# room.net
KiCad netlist of a schematic drawn in Altium Designer
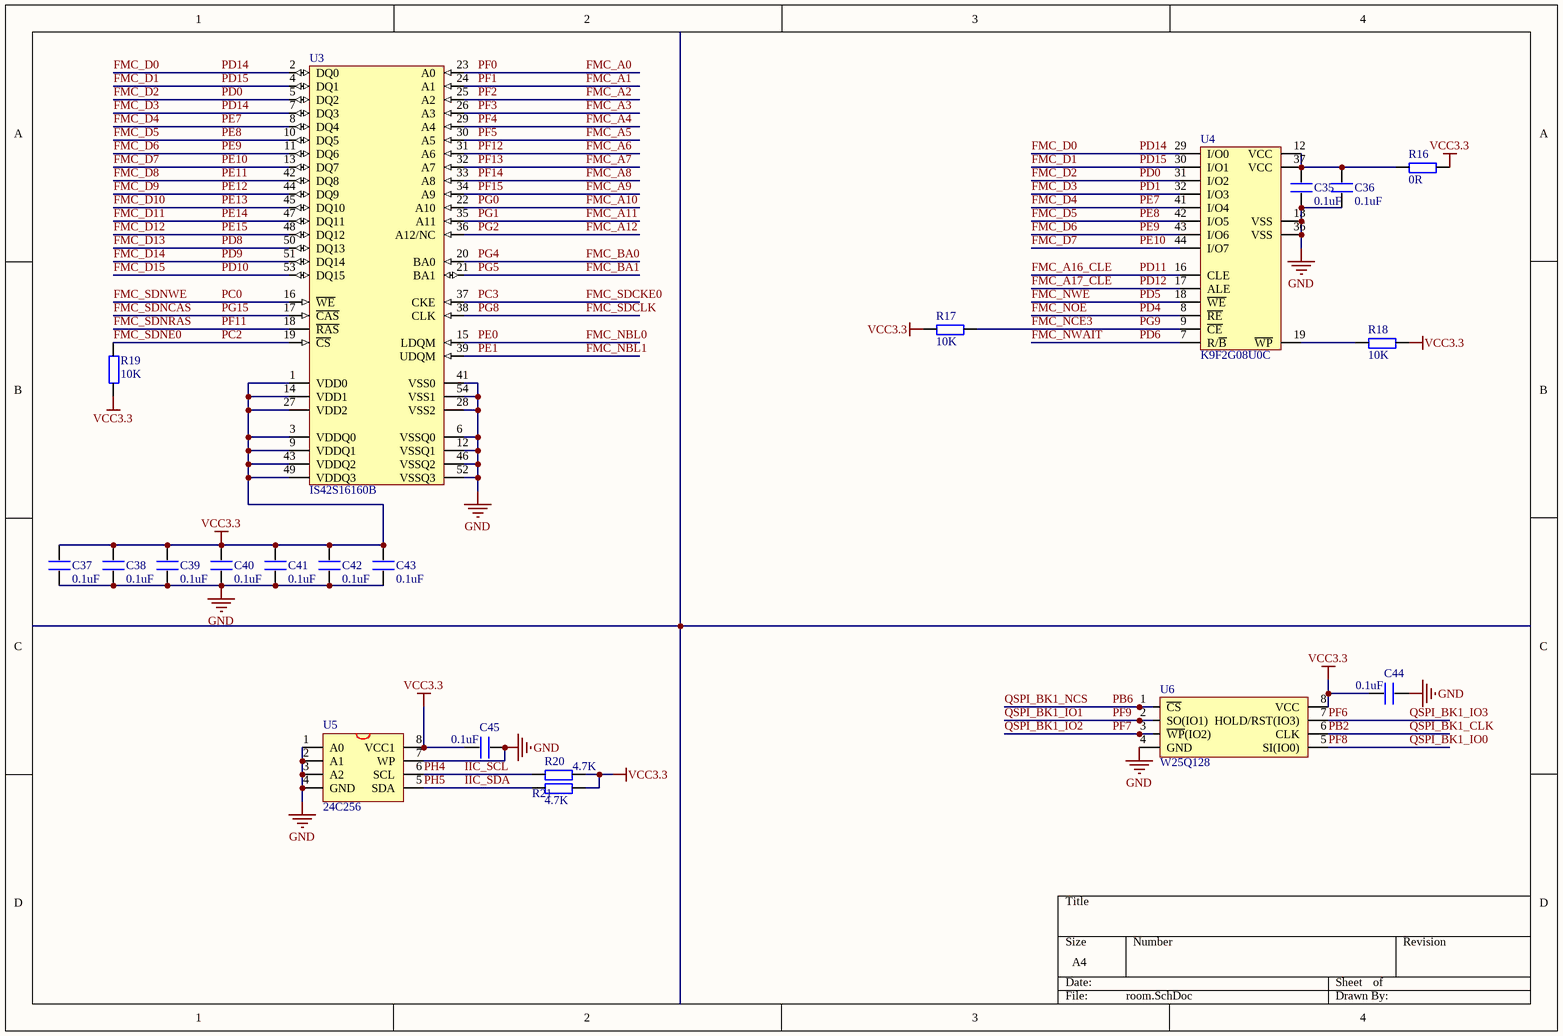
[diagram p0: room.SchDoc]

(export (version "E")
  (design (tool "Eeschema 10.0.6"))
  (components
    (comp (ref "C35") (value "0.1uF") (footprint "0402") (libsource (lib "STM32H743核心板封装库") (part "C")))
    (comp (ref "C36") (value "0.1uF") (footprint "0402") (libsource (lib "STM32H743核心板封装库") (part "C")))
    (comp (ref "C37") (value "0.1uF") (footprint "0402") (libsource (lib "STM32H743核心板封装库") (part "C")))
    (comp (ref "C38") (value "0.1uF") (footprint "0402") (libsource (lib "STM32H743核心板封装库") (part "C")))
    (comp (ref "C39") (value "0.1uF") (footprint "0402") (libsource (lib "STM32H743核心板封装库") (part "C")))
    (comp (ref "C40") (value "0.1uF") (footprint "0402") (libsource (lib "STM32H743核心板封装库") (part "C")))
    (comp (ref "C41") (value "0.1uF") (footprint "0402") (libsource (lib "STM32H743核心板封装库") (part "C")))
    (comp (ref "C42") (value "0.1uF") (footprint "0402") (libsource (lib "STM32H743核心板封装库") (part "C")))
    (comp (ref "C43") (value "0.1uF") (footprint "0402") (libsource (lib "STM32H743核心板封装库") (part "C")))
    (comp (ref "C44") (value "0.1uF") (footprint "0402") (libsource (lib "STM32H743核心板封装库") (part "C")))
    (comp (ref "C45") (value "0.1uF") (footprint "0402") (libsource (lib "STM32H743核心板封装库") (part "C")))
    (comp (ref "R16") (value "0R") (footprint "0402") (libsource (lib "STM32H743核心板封装库") (part "R")))
    (comp (ref "R17") (value "10K") (footprint "0402") (libsource (lib "STM32H743核心板封装库") (part "R")))
    (comp (ref "R18") (value "10K") (footprint "0402") (libsource (lib "STM32H743核心板封装库") (part "R")))
    (comp (ref "R19") (value "10K") (footprint "0402") (libsource (lib "STM32H743核心板封装库") (part "R")))
    (comp (ref "R20") (value "4.7K") (footprint "0402") (libsource (lib "STM32H743核心板封装库") (part "R")))
    (comp (ref "R21") (value "4.7K") (footprint "0402") (libsource (lib "STM32H743核心板封装库") (part "R")))
    (comp (ref "U3")
      (value "IS42S16160B")
      (footprint "TSOP54")
      (description "32MB SDRAM")
      (libsource (lib "STM32H743核心板封装库 V2.0_SCH") (part "IS42S16160B"))
    )
    (comp (ref "U4")
      (value "K9F2G08U0C")
      (footprint "TSOP48")
      (description "256MB NAND FLASH")
      (libsource (lib "STM32H743核心板封装库 V2.0_SCH") (part "K9F2G08U0C"))
    )
    (comp (ref "U5")
      (value "24C256")
      (footprint "SOP-8")
      (description "EEPROM")
      (libsource (lib "STM32H743核心板封装库 V2.0_SCH") (part "24C256"))
    )
    (comp (ref "U6")
      (value "W25Q128")
      (footprint "WSON8")
      (libsource (lib "STM32H743核心板封装库 V2.0_SCH") (part "W25Q128"))
    )
  )
  (nets
    (net (code "1") (name "/FMC_A0") (class "Default")
      (node (ref "U3") (pin "23") (pinfunction "A0_23") (pintype "input"))
    )
    (net (code "2") (name "/FMC_A1") (class "Default")
      (node (ref "U3") (pin "24") (pinfunction "A1_24") (pintype "input"))
    )
    (net (code "3") (name "/FMC_A2") (class "Default")
      (node (ref "U3") (pin "25") (pinfunction "A2_25") (pintype "input"))
    )
    (net (code "4") (name "/FMC_A3") (class "Default")
      (node (ref "U3") (pin "26") (pinfunction "A3_26") (pintype "input"))
    )
    (net (code "5") (name "/FMC_A4") (class "Default")
      (node (ref "U3") (pin "29") (pinfunction "A4_29") (pintype "input"))
    )
    (net (code "6") (name "/FMC_A5") (class "Default")
      (node (ref "U3") (pin "30") (pinfunction "A5_30") (pintype "input"))
    )
    (net (code "7") (name "/FMC_A6") (class "Default")
      (node (ref "U3") (pin "31") (pinfunction "A6_31") (pintype "input"))
    )
    (net (code "8") (name "/FMC_A7") (class "Default")
      (node (ref "U3") (pin "32") (pinfunction "A7_32") (pintype "input"))
    )
    (net (code "9") (name "/FMC_A8") (class "Default")
      (node (ref "U3") (pin "33") (pinfunction "A8_33") (pintype "input"))
    )
    (net (code "10") (name "/FMC_A9") (class "Default")
      (node (ref "U3") (pin "34") (pinfunction "A9_34") (pintype "input"))
    )
    (net (code "11") (name "/FMC_A10") (class "Default")
      (node (ref "U3") (pin "22") (pinfunction "A10_22") (pintype "input"))
    )
    (net (code "12") (name "/FMC_A11") (class "Default")
      (node (ref "U3") (pin "35") (pinfunction "A11_35") (pintype "input"))
    )
    (net (code "13") (name "/FMC_A12") (class "Default")
      (node (ref "U3") (pin "36") (pinfunction "A12/NC_36") (pintype "input"))
    )
    (net (code "14") (name "/FMC_A16_CLE") (class "Default")
      (node (ref "U4") (pin "16") (pinfunction "CLE_16") (pintype "passive"))
    )
    (net (code "15") (name "/FMC_A17_CLE") (class "Default")
      (node (ref "U4") (pin "17") (pinfunction "ALE_17") (pintype "passive"))
    )
    (net (code "16") (name "/FMC_BA0") (class "Default")
      (node (ref "U3") (pin "20") (pinfunction "BA0_20") (pintype "input"))
    )
    (net (code "17") (name "/FMC_BA1") (class "Default")
      (node (ref "U3") (pin "21") (pinfunction "BA1_21") (pintype "bidirectional"))
    )
    (net (code "18") (name "/FMC_D0") (class "Default")
      (node (ref "U3") (pin "2") (pinfunction "DQ0_2") (pintype "bidirectional"))
      (node (ref "U3") (pin "7") (pinfunction "DQ3_7") (pintype "bidirectional"))
      (node (ref "U4") (pin "29") (pinfunction "I/O0_29") (pintype "passive"))
      (node (ref "U4") (pin "32") (pinfunction "I/O3_32") (pintype "passive"))
    )
    (net (code "19") (name "/FMC_D1") (class "Default")
      (node (ref "U3") (pin "4") (pinfunction "DQ1_4") (pintype "bidirectional"))
      (node (ref "U4") (pin "30") (pinfunction "I/O1_30") (pintype "passive"))
    )
    (net (code "20") (name "/FMC_D2") (class "Default")
      (node (ref "U3") (pin "5") (pinfunction "DQ2_5") (pintype "bidirectional"))
      (node (ref "U4") (pin "31") (pinfunction "I/O2_31") (pintype "passive"))
    )
    (net (code "21") (name "/FMC_D4") (class "Default")
      (node (ref "U3") (pin "8") (pinfunction "DQ4_8") (pintype "bidirectional"))
      (node (ref "U4") (pin "41") (pinfunction "I/O4_41") (pintype "passive"))
    )
    (net (code "22") (name "/FMC_D5") (class "Default")
      (node (ref "U3") (pin "10") (pinfunction "DQ5_10") (pintype "bidirectional"))
      (node (ref "U4") (pin "42") (pinfunction "I/O5_42") (pintype "passive"))
    )
    (net (code "23") (name "/FMC_D6") (class "Default")
      (node (ref "U3") (pin "11") (pinfunction "DQ6_11") (pintype "bidirectional"))
      (node (ref "U4") (pin "43") (pinfunction "I/O6_43") (pintype "passive"))
    )
    (net (code "24") (name "/FMC_D7") (class "Default")
      (node (ref "U3") (pin "13") (pinfunction "DQ7_13") (pintype "bidirectional"))
      (node (ref "U4") (pin "44") (pinfunction "I/O7_44") (pintype "passive"))
    )
    (net (code "25") (name "/FMC_D8") (class "Default")
      (node (ref "U3") (pin "42") (pinfunction "DQ8_42") (pintype "bidirectional"))
    )
    (net (code "26") (name "/FMC_D9") (class "Default")
      (node (ref "U3") (pin "44") (pinfunction "DQ9_44") (pintype "bidirectional"))
    )
    (net (code "27") (name "/FMC_D10") (class "Default")
      (node (ref "U3") (pin "45") (pinfunction "DQ10_45") (pintype "bidirectional"))
    )
    (net (code "28") (name "/FMC_D11") (class "Default")
      (node (ref "U3") (pin "47") (pinfunction "DQ11_47") (pintype "bidirectional"))
    )
    (net (code "29") (name "/FMC_D12") (class "Default")
      (node (ref "U3") (pin "48") (pinfunction "DQ12_48") (pintype "bidirectional"))
    )
    (net (code "30") (name "/FMC_D13") (class "Default")
      (node (ref "U3") (pin "50") (pinfunction "DQ13_50") (pintype "bidirectional"))
    )
    (net (code "31") (name "/FMC_D14") (class "Default")
      (node (ref "U3") (pin "51") (pinfunction "DQ14_51") (pintype "bidirectional"))
    )
    (net (code "32") (name "/FMC_D15") (class "Default")
      (node (ref "U3") (pin "53") (pinfunction "DQ15_53") (pintype "bidirectional"))
    )
    (net (code "33") (name "/FMC_NBL0") (class "Default")
      (node (ref "U3") (pin "15") (pinfunction "LDQM_15") (pintype "input"))
    )
    (net (code "34") (name "/FMC_NBL1") (class "Default")
      (node (ref "U3") (pin "39") (pinfunction "UDQM_39") (pintype "input"))
    )
    (net (code "35") (name "/FMC_NCE3") (class "Default")
      (node (ref "R17") (pin "2") (pintype "passive"))
      (node (ref "U4") (pin "9") (pinfunction "~{CE}_9") (pintype "passive"))
    )
    (net (code "36") (name "/FMC_NOE") (class "Default")
      (node (ref "U4") (pin "8") (pinfunction "~{RE}_8") (pintype "passive"))
    )
    (net (code "37") (name "/FMC_NWAIT") (class "Default")
      (node (ref "U4") (pin "7") (pinfunction "R/~{B}_7") (pintype "passive"))
    )
    (net (code "38") (name "/FMC_NWE") (class "Default")
      (node (ref "U4") (pin "18") (pinfunction "~{WE}_18") (pintype "passive"))
    )
    (net (code "39") (name "/FMC_SDCKE0") (class "Default")
      (node (ref "U3") (pin "37") (pinfunction "CKE_37") (pintype "input"))
    )
    (net (code "40") (name "/FMC_SDCLK") (class "Default")
      (node (ref "U3") (pin "38") (pinfunction "CLK_38") (pintype "input"))
    )
    (net (code "41") (name "/FMC_SDNCAS") (class "Default")
      (node (ref "U3") (pin "17") (pinfunction "~{CAS}_17") (pintype "input"))
    )
    (net (code "42") (name "/FMC_SDNE0") (class "Default")
      (node (ref "R19") (pin "2") (pintype "passive"))
      (node (ref "U3") (pin "19") (pinfunction "~{CS}_19") (pintype "input"))
    )
    (net (code "43") (name "/FMC_SDNRAS") (class "Default")
      (node (ref "U3") (pin "18") (pinfunction "~{RAS}_18") (pintype "passive"))
    )
    (net (code "44") (name "/FMC_SDNWE") (class "Default")
      (node (ref "U3") (pin "16") (pinfunction "~{WE}_16") (pintype "input"))
    )
    (net (code "45") (name "/IIC_SCL") (class "Default")
      (node (ref "R20") (pin "1") (pintype "passive"))
      (node (ref "U5") (pin "6") (pinfunction "SCL_6") (pintype "passive"))
    )
    (net (code "46") (name "/IIC_SDA") (class "Default")
      (node (ref "R21") (pin "1") (pintype "passive"))
      (node (ref "U5") (pin "5") (pinfunction "SDA_5") (pintype "passive"))
    )
    (net (code "47") (name "/PB2") (class "Default")
      (node (ref "U6") (pin "6") (pinfunction "CLK_6") (pintype "passive"))
    )
    (net (code "48") (name "/PB6") (class "Default")
      (node (ref "U6") (pin "1") (pinfunction "~{CS}_1") (pintype "passive"))
    )
    (net (code "49") (name "/PF6") (class "Default")
      (node (ref "U6") (pin "7") (pinfunction "HOLD/RST(IO3)_7") (pintype "power_in"))
    )
    (net (code "50") (name "/PF7") (class "Default")
      (node (ref "U6") (pin "3") (pinfunction "~{WP}(IO2)_3") (pintype "passive"))
    )
    (net (code "51") (name "/PF8") (class "Default")
      (node (ref "U6") (pin "5") (pinfunction "SI(IO0)_5") (pintype "power_in"))
    )
    (net (code "52") (name "/PF9") (class "Default")
      (node (ref "U6") (pin "2") (pinfunction "SO(IO1)_2") (pintype "passive"))
    )
    (net (code "53") (name "GND") (class "Default")
      (node (ref "C35") (pin "1") (pintype "passive"))
      (node (ref "C36") (pin "1") (pintype "passive"))
      (node (ref "C37") (pin "1") (pintype "passive"))
      (node (ref "C38") (pin "1") (pintype "passive"))
      (node (ref "C39") (pin "1") (pintype "passive"))
      (node (ref "C40") (pin "1") (pintype "passive"))
      (node (ref "C41") (pin "1") (pintype "passive"))
      (node (ref "C42") (pin "1") (pintype "passive"))
      (node (ref "C43") (pin "1") (pintype "passive"))
      (node (ref "C44") (pin "2") (pintype "passive"))
      (node (ref "C45") (pin "2") (pintype "passive"))
      (node (ref "U3") (pin "12") (pinfunction "VSSQ1_12") (pintype "power_in"))
      (node (ref "U3") (pin "28") (pinfunction "VSS2_28") (pintype "power_in"))
      (node (ref "U3") (pin "41") (pinfunction "VSS0_41") (pintype "power_in"))
      (node (ref "U3") (pin "46") (pinfunction "VSSQ2_46") (pintype "power_in"))
      (node (ref "U3") (pin "52") (pinfunction "VSSQ3_52") (pintype "power_in"))
      (node (ref "U3") (pin "54") (pinfunction "VSS1_54") (pintype "power_in"))
      (node (ref "U3") (pin "6") (pinfunction "VSSQ0_6") (pintype "power_in"))
      (node (ref "U4") (pin "13") (pinfunction "VSS_13") (pintype "passive"))
      (node (ref "U4") (pin "36") (pinfunction "VSS_36") (pintype "passive"))
      (node (ref "U5") (pin "1") (pinfunction "A0_1") (pintype "passive"))
      (node (ref "U5") (pin "2") (pinfunction "A1_2") (pintype "passive"))
      (node (ref "U5") (pin "3") (pinfunction "A2_3") (pintype "passive"))
      (node (ref "U5") (pin "4") (pinfunction "GND_4") (pintype "passive"))
      (node (ref "U5") (pin "7") (pinfunction "WP_7") (pintype "passive"))
      (node (ref "U6") (pin "4") (pinfunction "GND_4") (pintype "passive"))
    )
    (net (code "54") (name "Net-(C35-Pad2)") (class "Default")
      (node (ref "C35") (pin "2") (pintype "passive"))
      (node (ref "C36") (pin "2") (pintype "passive"))
      (node (ref "R16") (pin "1") (pintype "passive"))
      (node (ref "U4") (pin "12") (pinfunction "VCC_12") (pintype "passive"))
      (node (ref "U4") (pin "37") (pinfunction "VCC_37") (pintype "passive"))
    )
    (net (code "55") (name "Net-(U4-~{WP})") (class "Default")
      (node (ref "R18") (pin "1") (pintype "passive"))
      (node (ref "U4") (pin "19") (pinfunction "~{WP}_19") (pintype "passive"))
    )
    (net (code "56") (name "VCC3.3") (class "Default")
      (node (ref "C37") (pin "2") (pintype "passive"))
      (node (ref "C38") (pin "2") (pintype "passive"))
      (node (ref "C39") (pin "2") (pintype "passive"))
      (node (ref "C40") (pin "2") (pintype "passive"))
      (node (ref "C41") (pin "2") (pintype "passive"))
      (node (ref "C42") (pin "2") (pintype "passive"))
      (node (ref "C43") (pin "2") (pintype "passive"))
      (node (ref "C44") (pin "1") (pintype "passive"))
      (node (ref "C45") (pin "1") (pintype "passive"))
      (node (ref "R16") (pin "2") (pintype "passive"))
      (node (ref "R17") (pin "1") (pintype "passive"))
      (node (ref "R18") (pin "2") (pintype "passive"))
      (node (ref "R19") (pin "1") (pintype "passive"))
      (node (ref "R20") (pin "2") (pintype "passive"))
      (node (ref "R21") (pin "2") (pintype "passive"))
      (node (ref "U3") (pin "1") (pinfunction "VDD0_1") (pintype "power_in"))
      (node (ref "U3") (pin "14") (pinfunction "VDD1_14") (pintype "power_in"))
      (node (ref "U3") (pin "27") (pinfunction "VDD2_27") (pintype "power_in"))
      (node (ref "U3") (pin "3") (pinfunction "VDDQ0_3") (pintype "power_in"))
      (node (ref "U3") (pin "43") (pinfunction "VDDQ2_43") (pintype "power_in"))
      (node (ref "U3") (pin "49") (pinfunction "VDDQ3_49") (pintype "power_in"))
      (node (ref "U3") (pin "9") (pinfunction "VDDQ1_9") (pintype "power_in"))
      (node (ref "U5") (pin "8") (pinfunction "VCC1_8") (pintype "passive"))
      (node (ref "U6") (pin "8") (pinfunction "VCC_8") (pintype "passive"))
    )
  )
)
